# Controller_Power_Sliced.net
KiCad netlist of a schematic drawn in EAGLE
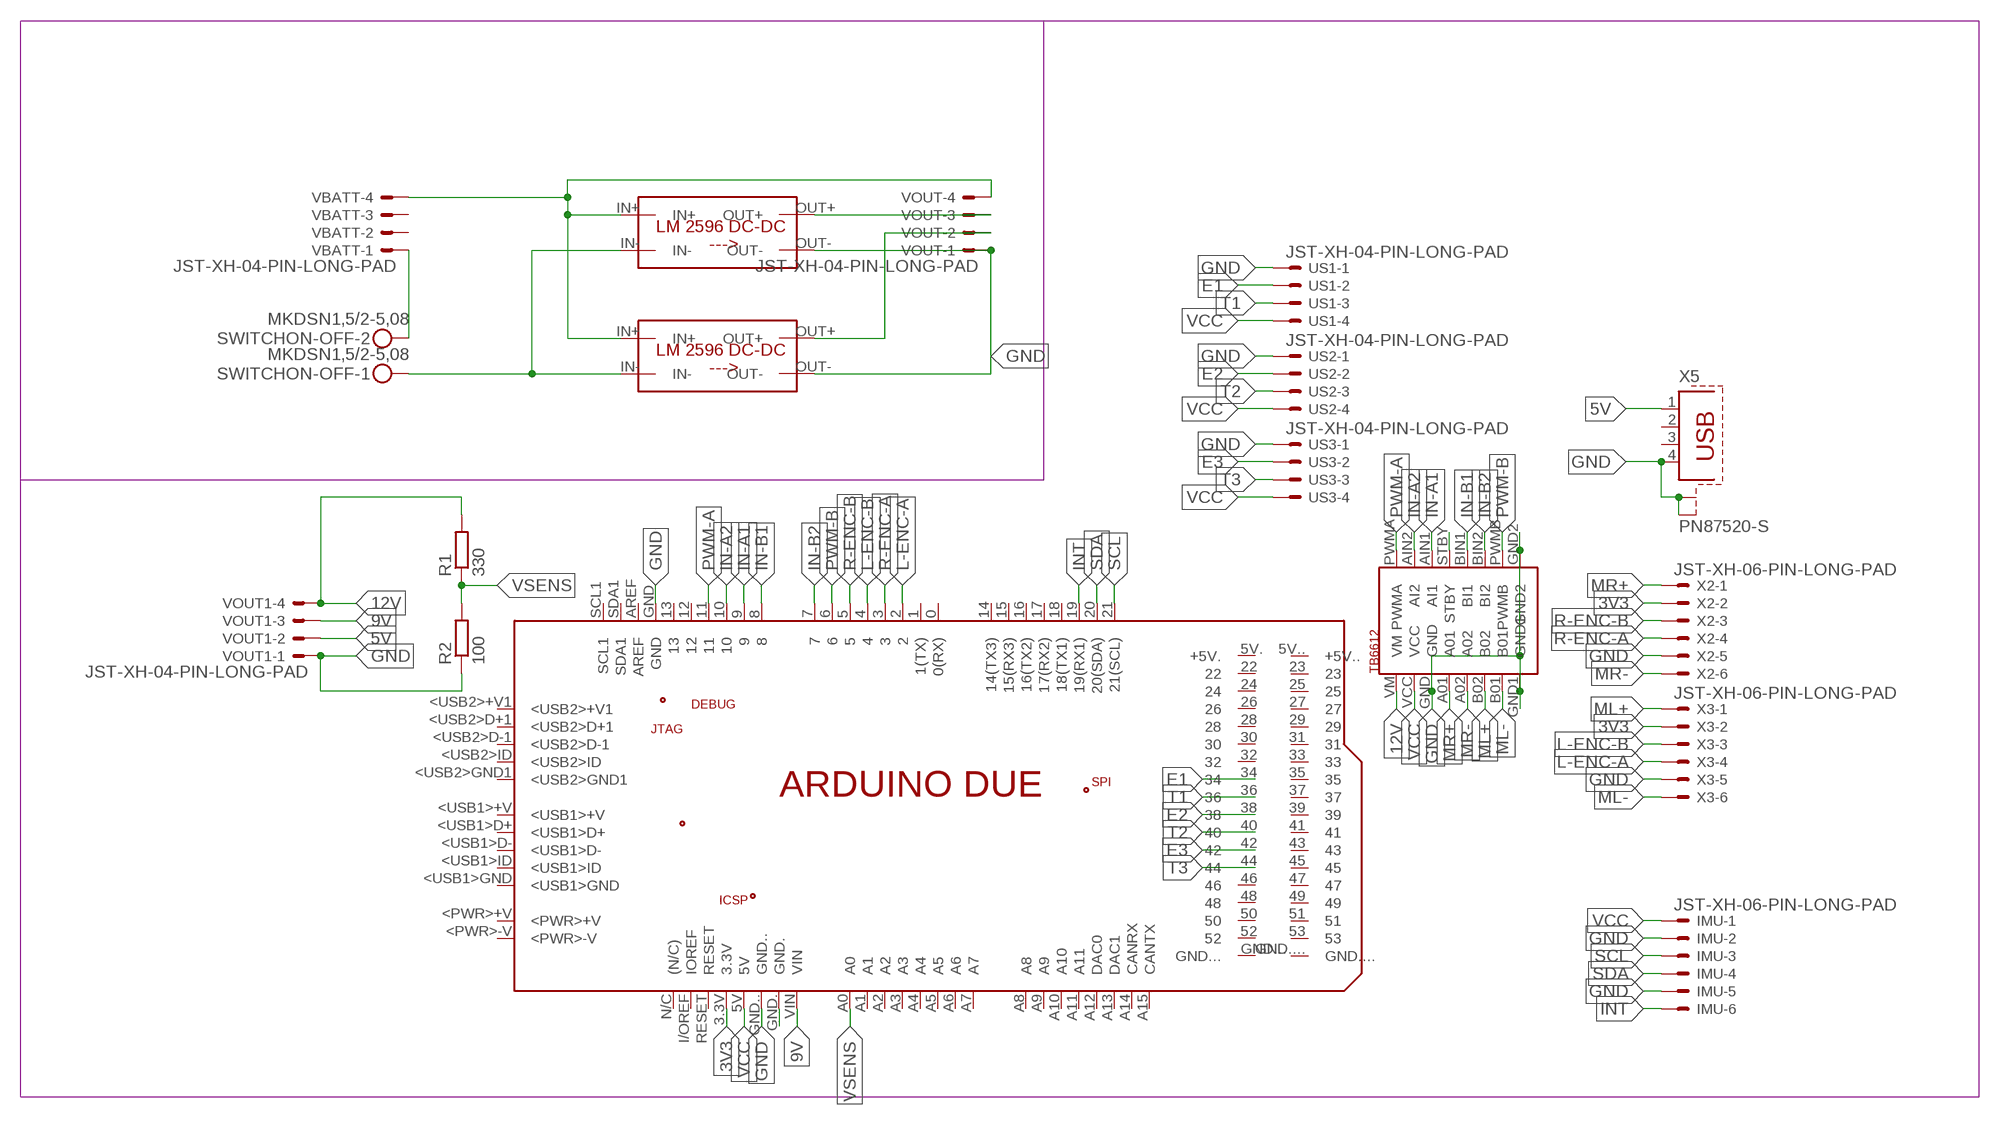
[diagram p0: schematic, sheet 1]

(export (version "E")
  (design (tool "Eeschema 10.0.6"))
  (components
    (comp (ref "IMU")
      (value "JST-XH-06-PIN-LONG-PAD")
      (footprint "eagle-import:JST-XH-06-PACKAGE-LONG-PAD")
      (libsource (lib "eagle-import") (part "JST-XH-06-PIN-LONG-PAD"))
    )
    (comp (ref "PCB1")
      (value "ARDUINO_DUE")
      (footprint "eagle-import:ARDUINO_DUE")
      (libsource (lib "eagle-import") (part "ARDUINO_DUE"))
    )
    (comp (ref "R1")
      (value "330")
      (footprint "eagle-import:R1206")
      (libsource (lib "eagle-import") (part "R-EU_R1206"))
    )
    (comp (ref "R2")
      (value "100")
      (footprint "eagle-import:R1206")
      (libsource (lib "eagle-import") (part "R-EU_R1206"))
    )
    (comp (ref "SWITCHON-OFF")
      (value "MKDSN1,5/2-5,08")
      (footprint "eagle-import:MKDSN1,5_2-5,08")
      (libsource (lib "eagle-import") (part "MKDSN1,5/2-5,08"))
    )
    (comp (ref "U$1")
      (value "LM2596_MODBUCK")
      (footprint "eagle-import:LM2596_MOD")
      (libsource (lib "eagle-import") (part "LM2596_MODBUCK"))
    )
    (comp (ref "U$2")
      (value "LM2596_MODBUCK")
      (footprint "eagle-import:LM2596_MOD")
      (libsource (lib "eagle-import") (part "LM2596_MODBUCK"))
    )
    (comp (ref "U$3")
      (value "TB6612")
      (footprint "eagle-import:TB6612")
      (libsource (lib "eagle-import") (part "TB6612"))
    )
    (comp (ref "US1")
      (value "JST-XH-04-PIN-LONG-PAD")
      (footprint "eagle-import:JST-XH-04-PACKAGE-LONG-PAD")
      (libsource (lib "eagle-import") (part "JST-XH-04-PIN-LONG-PAD"))
    )
    (comp (ref "US2")
      (value "JST-XH-04-PIN-LONG-PAD")
      (footprint "eagle-import:JST-XH-04-PACKAGE-LONG-PAD")
      (libsource (lib "eagle-import") (part "JST-XH-04-PIN-LONG-PAD"))
    )
    (comp (ref "US3")
      (value "JST-XH-04-PIN-LONG-PAD")
      (footprint "eagle-import:JST-XH-04-PACKAGE-LONG-PAD")
      (libsource (lib "eagle-import") (part "JST-XH-04-PIN-LONG-PAD"))
    )
    (comp (ref "VBATT")
      (value "JST-XH-04-PIN-LONG-PAD")
      (footprint "eagle-import:JST-XH-04-PACKAGE-LONG-PAD")
      (libsource (lib "eagle-import") (part "JST-XH-04-PIN-LONG-PAD"))
    )
    (comp (ref "VOUT")
      (value "JST-XH-04-PIN-LONG-PAD")
      (footprint "eagle-import:JST-XH-04-PACKAGE-LONG-PAD")
      (libsource (lib "eagle-import") (part "JST-XH-04-PIN-LONG-PAD"))
    )
    (comp (ref "VOUT1")
      (value "JST-XH-04-PIN-LONG-PAD")
      (footprint "eagle-import:JST-XH-04-PACKAGE-LONG-PAD")
      (libsource (lib "eagle-import") (part "JST-XH-04-PIN-LONG-PAD"))
    )
    (comp (ref "X2")
      (value "JST-XH-06-PIN-LONG-PAD")
      (footprint "eagle-import:JST-XH-06-PACKAGE-LONG-PAD")
      (libsource (lib "eagle-import") (part "JST-XH-06-PIN-LONG-PAD"))
    )
    (comp (ref "X3")
      (value "JST-XH-06-PIN-LONG-PAD")
      (footprint "eagle-import:JST-XH-06-PACKAGE-LONG-PAD")
      (libsource (lib "eagle-import") (part "JST-XH-06-PIN-LONG-PAD"))
    )
    (comp (ref "X5")
      (value "PN87520-S")
      (footprint "eagle-import:PN87520-S")
      (libsource (lib "eagle-import") (part "PN87520-S"))
    )
  )
  (nets
    (net (code "1") (name "3V3") (class "Default")
      (node (ref "PCB1") (pin "3.3V") (pinfunction "3.3V_3.3V") (pintype "bidirectional"))
      (node (ref "X2") (pin "2") (pinfunction "S_2") (pintype "passive"))
      (node (ref "X3") (pin "2") (pinfunction "S_2") (pintype "passive"))
    )
    (net (code "2") (name "5V") (class "Default")
      (node (ref "VOUT1") (pin "2") (pinfunction "S_2") (pintype "passive"))
      (node (ref "X5") (pin "1") (pinfunction "1_1") (pintype "passive"))
    )
    (net (code "3") (name "9V") (class "Default")
      (node (ref "PCB1") (pin "VIN") (pinfunction "VIN_VIN") (pintype "bidirectional"))
      (node (ref "VOUT1") (pin "3") (pinfunction "S_3") (pintype "passive"))
    )
    (net (code "4") (name "12V") (class "Default")
      (node (ref "R1") (pin "2") (pinfunction "2_2") (pintype "passive"))
      (node (ref "U$3") (pin "VM") (pinfunction "VM_VM") (pintype "bidirectional"))
      (node (ref "VOUT1") (pin "4") (pinfunction "S_4") (pintype "passive"))
    )
    (net (code "5") (name "E1") (class "Default")
      (node (ref "PCB1") (pin "34") (pinfunction "34_34") (pintype "bidirectional"))
      (node (ref "US1") (pin "2") (pinfunction "S_2") (pintype "passive"))
    )
    (net (code "6") (name "E2") (class "Default")
      (node (ref "PCB1") (pin "38") (pinfunction "38_38") (pintype "bidirectional"))
      (node (ref "US2") (pin "2") (pinfunction "S_2") (pintype "passive"))
    )
    (net (code "7") (name "E3") (class "Default")
      (node (ref "PCB1") (pin "42") (pinfunction "42_42") (pintype "bidirectional"))
      (node (ref "US3") (pin "2") (pinfunction "S_2") (pintype "passive"))
    )
    (net (code "8") (name "GND") (class "Default")
      (node (ref "IMU") (pin "2") (pinfunction "S_2") (pintype "passive"))
      (node (ref "IMU") (pin "5") (pinfunction "S_5") (pintype "passive"))
      (node (ref "PCB1") (pin "GND") (pinfunction "GND_GND") (pintype "bidirectional"))
      (node (ref "PCB1") (pin "GND..") (pinfunction "GND.._GND..") (pintype "bidirectional"))
      (node (ref "R2") (pin "1") (pinfunction "1_1") (pintype "passive"))
      (node (ref "U$1") (pin "OUT-") (pinfunction "OUT-_OUT-") (pintype "bidirectional"))
      (node (ref "U$2") (pin "OUT-") (pinfunction "OUT-_OUT-") (pintype "bidirectional"))
      (node (ref "U$3") (pin "GND") (pinfunction "GND_GND") (pintype "power_in"))
      (node (ref "U$3") (pin "GND1") (pinfunction "GND1_GND1") (pintype "power_in"))
      (node (ref "U$3") (pin "GND2") (pinfunction "GND2_GND2") (pintype "power_in"))
      (node (ref "US1") (pin "1") (pinfunction "S_1") (pintype "passive"))
      (node (ref "US2") (pin "1") (pinfunction "S_1") (pintype "passive"))
      (node (ref "US3") (pin "1") (pinfunction "S_1") (pintype "passive"))
      (node (ref "VOUT") (pin "1") (pinfunction "S_1") (pintype "passive"))
      (node (ref "VOUT1") (pin "1") (pinfunction "S_1") (pintype "passive"))
      (node (ref "X2") (pin "5") (pinfunction "S_5") (pintype "passive"))
      (node (ref "X3") (pin "5") (pinfunction "S_5") (pintype "passive"))
      (node (ref "X5") (pin "4") (pinfunction "4_4") (pintype "passive"))
      (node (ref "X5") (pin "S1") (pinfunction "S1_S1") (pintype "passive"))
      (node (ref "X5") (pin "S2") (pinfunction "S2_S2") (pintype "passive"))
    )
    (net (code "9") (name "IN-A1") (class "Default")
      (node (ref "PCB1") (pin "9") (pinfunction "9_9") (pintype "bidirectional"))
      (node (ref "U$3") (pin "AIN1") (pinfunction "AI1_AIN1") (pintype "bidirectional"))
    )
    (net (code "10") (name "IN-A2") (class "Default")
      (node (ref "PCB1") (pin "10") (pinfunction "10_10") (pintype "bidirectional"))
      (node (ref "U$3") (pin "AIN2") (pinfunction "AI2_AIN2") (pintype "bidirectional"))
    )
    (net (code "11") (name "IN-B1") (class "Default")
      (node (ref "PCB1") (pin "8") (pinfunction "8_8") (pintype "bidirectional"))
      (node (ref "U$3") (pin "BIN1") (pinfunction "BI1_BIN1") (pintype "bidirectional"))
    )
    (net (code "12") (name "IN-B2") (class "Default")
      (node (ref "PCB1") (pin "7") (pinfunction "7_7") (pintype "bidirectional"))
      (node (ref "U$3") (pin "BIN2") (pinfunction "BI2_BIN2") (pintype "bidirectional"))
    )
    (net (code "13") (name "INT") (class "Default")
      (node (ref "IMU") (pin "6") (pinfunction "S_6") (pintype "passive"))
      (node (ref "PCB1") (pin "19") (pinfunction "19(RX1)_19") (pintype "bidirectional"))
    )
    (net (code "14") (name "L-ENC-A") (class "Default")
      (node (ref "PCB1") (pin "2") (pinfunction "2_2") (pintype "bidirectional"))
      (node (ref "X3") (pin "4") (pinfunction "S_4") (pintype "passive"))
    )
    (net (code "15") (name "L-ENC-B") (class "Default")
      (node (ref "PCB1") (pin "4") (pinfunction "4_4") (pintype "bidirectional"))
      (node (ref "X3") (pin "3") (pinfunction "S_3") (pintype "passive"))
    )
    (net (code "16") (name "ML+") (class "Default")
      (node (ref "U$3") (pin "B02") (pinfunction "B02_B02") (pintype "bidirectional"))
      (node (ref "X3") (pin "1") (pinfunction "S_1") (pintype "passive"))
    )
    (net (code "17") (name "ML-") (class "Default")
      (node (ref "U$3") (pin "B01") (pinfunction "B01_B01") (pintype "bidirectional"))
      (node (ref "X3") (pin "6") (pinfunction "S_6") (pintype "passive"))
    )
    (net (code "18") (name "MR+") (class "Default")
      (node (ref "U$3") (pin "A01") (pinfunction "A01_A01") (pintype "bidirectional"))
      (node (ref "X2") (pin "1") (pinfunction "S_1") (pintype "passive"))
    )
    (net (code "19") (name "MR-") (class "Default")
      (node (ref "U$3") (pin "A02") (pinfunction "A02_A02") (pintype "bidirectional"))
      (node (ref "X2") (pin "6") (pinfunction "S_6") (pintype "passive"))
    )
    (net (code "20") (name "Net-(SWITCHON-OFFA-KL)") (class "Default")
      (node (ref "SWITCHON-OFF") (pin "1") (pinfunction "KL_1") (pintype "passive"))
      (node (ref "U$1") (pin "IN-") (pinfunction "IN-_IN-") (pintype "bidirectional"))
      (node (ref "U$2") (pin "IN-") (pinfunction "IN-_IN-") (pintype "bidirectional"))
    )
    (net (code "21") (name "Net-(SWITCHON-OFFB-KL)") (class "Default")
      (node (ref "SWITCHON-OFF") (pin "2") (pinfunction "KL_2") (pintype "passive"))
      (node (ref "VBATT") (pin "1") (pinfunction "S_1") (pintype "passive"))
    )
    (net (code "22") (name "Net-(VBATTD-S)") (class "Default")
      (node (ref "U$1") (pin "IN+") (pinfunction "IN+_IN+") (pintype "bidirectional"))
      (node (ref "U$2") (pin "IN+") (pinfunction "IN+_IN+") (pintype "bidirectional"))
      (node (ref "VBATT") (pin "4") (pinfunction "S_4") (pintype "passive"))
      (node (ref "VOUT") (pin "4") (pinfunction "S_4") (pintype "passive"))
    )
    (net (code "23") (name "Net-(VOUTB-S)") (class "Default")
      (node (ref "U$1") (pin "OUT+") (pinfunction "OUT+_OUT+") (pintype "bidirectional"))
      (node (ref "VOUT") (pin "2") (pinfunction "S_2") (pintype "passive"))
    )
    (net (code "24") (name "Net-(VOUTC-S)") (class "Default")
      (node (ref "U$2") (pin "OUT+") (pinfunction "OUT+_OUT+") (pintype "bidirectional"))
      (node (ref "VOUT") (pin "3") (pinfunction "S_3") (pintype "passive"))
    )
    (net (code "25") (name "PWM-A") (class "Default")
      (node (ref "PCB1") (pin "11") (pinfunction "11_11") (pintype "bidirectional"))
      (node (ref "U$3") (pin "PWMA") (pinfunction "PWMA_PWMA") (pintype "bidirectional"))
    )
    (net (code "26") (name "PWM-B") (class "Default")
      (node (ref "PCB1") (pin "6") (pinfunction "6_6") (pintype "bidirectional"))
      (node (ref "U$3") (pin "PWMB") (pinfunction "PWMB_PWMB") (pintype "bidirectional"))
    )
    (net (code "27") (name "R-ENC-A") (class "Default")
      (node (ref "PCB1") (pin "3") (pinfunction "3_3") (pintype "bidirectional"))
      (node (ref "X2") (pin "4") (pinfunction "S_4") (pintype "passive"))
    )
    (net (code "28") (name "R-ENC-B") (class "Default")
      (node (ref "PCB1") (pin "5") (pinfunction "5_5") (pintype "bidirectional"))
      (node (ref "X2") (pin "3") (pinfunction "S_3") (pintype "passive"))
    )
    (net (code "29") (name "SCL") (class "Default")
      (node (ref "IMU") (pin "3") (pinfunction "S_3") (pintype "passive"))
      (node (ref "PCB1") (pin "21") (pinfunction "21(SCL)_21") (pintype "bidirectional"))
    )
    (net (code "30") (name "SDA") (class "Default")
      (node (ref "IMU") (pin "4") (pinfunction "S_4") (pintype "passive"))
      (node (ref "PCB1") (pin "20") (pinfunction "20(SDA)_20") (pintype "bidirectional"))
    )
    (net (code "31") (name "T1") (class "Default")
      (node (ref "PCB1") (pin "36") (pinfunction "36_36") (pintype "bidirectional"))
      (node (ref "US1") (pin "3") (pinfunction "S_3") (pintype "passive"))
    )
    (net (code "32") (name "T2") (class "Default")
      (node (ref "PCB1") (pin "40") (pinfunction "40_40") (pintype "bidirectional"))
      (node (ref "US2") (pin "3") (pinfunction "S_3") (pintype "passive"))
    )
    (net (code "33") (name "T3") (class "Default")
      (node (ref "PCB1") (pin "44") (pinfunction "44_44") (pintype "bidirectional"))
      (node (ref "US3") (pin "3") (pinfunction "S_3") (pintype "passive"))
    )
    (net (code "34") (name "VCC") (class "Default")
      (node (ref "IMU") (pin "1") (pinfunction "S_1") (pintype "passive"))
      (node (ref "PCB1") (pin "5V") (pinfunction "5V_5V") (pintype "bidirectional"))
      (node (ref "U$3") (pin "VCC") (pinfunction "VCC_VCC") (pintype "bidirectional"))
      (node (ref "US1") (pin "4") (pinfunction "S_4") (pintype "passive"))
      (node (ref "US2") (pin "4") (pinfunction "S_4") (pintype "passive"))
      (node (ref "US3") (pin "4") (pinfunction "S_4") (pintype "passive"))
    )
    (net (code "35") (name "VSENS") (class "Default")
      (node (ref "PCB1") (pin "A0") (pinfunction "A0_A0") (pintype "bidirectional"))
      (node (ref "R1") (pin "1") (pinfunction "1_1") (pintype "passive"))
      (node (ref "R2") (pin "2") (pinfunction "2_2") (pintype "passive"))
    )
    (net (code "36") (name "unconnected-(PCB1-(N{slash}C)-PadN{slash}C)") (class "Default")
      (node (ref "PCB1") (pin "N/C") (pinfunction "(N/C)_N/C") (pintype "bidirectional"))
    )
    (net (code "37") (name "unconnected-(PCB1-+5V.-Pad5V.)") (class "Default")
      (node (ref "PCB1") (pin "5V.") (pinfunction "+5V._5V.") (pintype "bidirectional"))
    )
    (net (code "38") (name "unconnected-(PCB1-+5V..-Pad5V..)") (class "Default")
      (node (ref "PCB1") (pin "5V..") (pinfunction "+5V.._5V..") (pintype "bidirectional"))
    )
    (net (code "39") (name "unconnected-(PCB1-0(RX)-Pad0)") (class "Default")
      (node (ref "PCB1") (pin "0") (pinfunction "0(RX)_0") (pintype "bidirectional"))
    )
    (net (code "40") (name "unconnected-(PCB1-1(TX)-Pad1)") (class "Default")
      (node (ref "PCB1") (pin "1") (pinfunction "1(TX)_1") (pintype "bidirectional"))
    )
    (net (code "41") (name "unconnected-(PCB1-14(TX3)-Pad14)") (class "Default")
      (node (ref "PCB1") (pin "14") (pinfunction "14(TX3)_14") (pintype "bidirectional"))
    )
    (net (code "42") (name "unconnected-(PCB1-15(RX3)-Pad15)") (class "Default")
      (node (ref "PCB1") (pin "15") (pinfunction "15(RX3)_15") (pintype "bidirectional"))
    )
    (net (code "43") (name "unconnected-(PCB1-16(TX2)-Pad16)") (class "Default")
      (node (ref "PCB1") (pin "16") (pinfunction "16(TX2)_16") (pintype "bidirectional"))
    )
    (net (code "44") (name "unconnected-(PCB1-17(RX2)-Pad17)") (class "Default")
      (node (ref "PCB1") (pin "17") (pinfunction "17(RX2)_17") (pintype "bidirectional"))
    )
    (net (code "45") (name "unconnected-(PCB1-18(TX1)-Pad18)") (class "Default")
      (node (ref "PCB1") (pin "18") (pinfunction "18(TX1)_18") (pintype "bidirectional"))
    )
    (net (code "46") (name "unconnected-(PCB1-CANRX-PadA14)") (class "Default")
      (node (ref "PCB1") (pin "A14") (pinfunction "CANRX_A14") (pintype "bidirectional"))
    )
    (net (code "47") (name "unconnected-(PCB1-CANTX-PadA15)") (class "Default")
      (node (ref "PCB1") (pin "A15") (pinfunction "CANTX_A15") (pintype "bidirectional"))
    )
    (net (code "48") (name "unconnected-(PCB1-DAC0-PadA12)") (class "Default")
      (node (ref "PCB1") (pin "A12") (pinfunction "DAC0_A12") (pintype "bidirectional"))
    )
    (net (code "49") (name "unconnected-(PCB1-DAC1-PadA13)") (class "Default")
      (node (ref "PCB1") (pin "A13") (pinfunction "DAC1_A13") (pintype "bidirectional"))
    )
    (net (code "50") (name "unconnected-(PCB1-IOREF-PadI{slash}OREF)") (class "Default")
      (node (ref "PCB1") (pin "I/OREF") (pinfunction "IOREF_I/OREF") (pintype "bidirectional"))
    )
    (net (code "51") (name "unconnected-(PCB1-Pad+3.3V)") (class "Default")
      (node (ref "PCB1") (pin "+3.3V") (pinfunction "+3.3V_+3.3V") (pintype "bidirectional"))
    )
    (net (code "52") (name "unconnected-(PCB1-Pad+5V)") (class "Default")
      (node (ref "PCB1") (pin "+5V") (pinfunction "+5V_+5V") (pintype "bidirectional"))
    )
    (net (code "53") (name "unconnected-(PCB1-Pad+5V_)") (class "Default")
      (node (ref "PCB1") (pin "+5V_") (pinfunction "+5V__+5V_") (pintype "bidirectional"))
    )
    (net (code "54") (name "unconnected-(PCB1-Pad12)") (class "Default")
      (node (ref "PCB1") (pin "12") (pinfunction "12_12") (pintype "bidirectional"))
    )
    (net (code "55") (name "unconnected-(PCB1-Pad13)") (class "Default")
      (node (ref "PCB1") (pin "13") (pinfunction "13_13") (pintype "bidirectional"))
    )
    (net (code "56") (name "unconnected-(PCB1-Pad22)") (class "Default")
      (node (ref "PCB1") (pin "22") (pinfunction "22_22") (pintype "bidirectional"))
    )
    (net (code "57") (name "unconnected-(PCB1-Pad23)") (class "Default")
      (node (ref "PCB1") (pin "23") (pinfunction "23_23") (pintype "bidirectional"))
    )
    (net (code "58") (name "unconnected-(PCB1-Pad24)") (class "Default")
      (node (ref "PCB1") (pin "24") (pinfunction "24_24") (pintype "bidirectional"))
    )
    (net (code "59") (name "unconnected-(PCB1-Pad25)") (class "Default")
      (node (ref "PCB1") (pin "25") (pinfunction "25_25") (pintype "bidirectional"))
    )
    (net (code "60") (name "unconnected-(PCB1-Pad26)") (class "Default")
      (node (ref "PCB1") (pin "26") (pinfunction "26_26") (pintype "bidirectional"))
    )
    (net (code "61") (name "unconnected-(PCB1-Pad27)") (class "Default")
      (node (ref "PCB1") (pin "27") (pinfunction "27_27") (pintype "bidirectional"))
    )
    (net (code "62") (name "unconnected-(PCB1-Pad28)") (class "Default")
      (node (ref "PCB1") (pin "28") (pinfunction "28_28") (pintype "bidirectional"))
    )
    (net (code "63") (name "unconnected-(PCB1-Pad29)") (class "Default")
      (node (ref "PCB1") (pin "29") (pinfunction "29_29") (pintype "bidirectional"))
    )
    (net (code "64") (name "unconnected-(PCB1-Pad30)") (class "Default")
      (node (ref "PCB1") (pin "30") (pinfunction "30_30") (pintype "bidirectional"))
    )
    (net (code "65") (name "unconnected-(PCB1-Pad31)") (class "Default")
      (node (ref "PCB1") (pin "31") (pinfunction "31_31") (pintype "bidirectional"))
    )
    (net (code "66") (name "unconnected-(PCB1-Pad32)") (class "Default")
      (node (ref "PCB1") (pin "32") (pinfunction "32_32") (pintype "bidirectional"))
    )
    (net (code "67") (name "unconnected-(PCB1-Pad33)") (class "Default")
      (node (ref "PCB1") (pin "33") (pinfunction "33_33") (pintype "bidirectional"))
    )
    (net (code "68") (name "unconnected-(PCB1-Pad35)") (class "Default")
      (node (ref "PCB1") (pin "35") (pinfunction "35_35") (pintype "bidirectional"))
    )
    (net (code "69") (name "unconnected-(PCB1-Pad37)") (class "Default")
      (node (ref "PCB1") (pin "37") (pinfunction "37_37") (pintype "bidirectional"))
    )
    (net (code "70") (name "unconnected-(PCB1-Pad39)") (class "Default")
      (node (ref "PCB1") (pin "39") (pinfunction "39_39") (pintype "bidirectional"))
    )
    (net (code "71") (name "unconnected-(PCB1-Pad41)") (class "Default")
      (node (ref "PCB1") (pin "41") (pinfunction "41_41") (pintype "bidirectional"))
    )
    (net (code "72") (name "unconnected-(PCB1-Pad43)") (class "Default")
      (node (ref "PCB1") (pin "43") (pinfunction "43_43") (pintype "bidirectional"))
    )
    (net (code "73") (name "unconnected-(PCB1-Pad45)") (class "Default")
      (node (ref "PCB1") (pin "45") (pinfunction "45_45") (pintype "bidirectional"))
    )
    (net (code "74") (name "unconnected-(PCB1-Pad46)") (class "Default")
      (node (ref "PCB1") (pin "46") (pinfunction "46_46") (pintype "bidirectional"))
    )
    (net (code "75") (name "unconnected-(PCB1-Pad47)") (class "Default")
      (node (ref "PCB1") (pin "47") (pinfunction "47_47") (pintype "bidirectional"))
    )
    (net (code "76") (name "unconnected-(PCB1-Pad48)") (class "Default")
      (node (ref "PCB1") (pin "48") (pinfunction "48_48") (pintype "bidirectional"))
    )
    (net (code "77") (name "unconnected-(PCB1-Pad49)") (class "Default")
      (node (ref "PCB1") (pin "49") (pinfunction "49_49") (pintype "bidirectional"))
    )
    (net (code "78") (name "unconnected-(PCB1-Pad50)") (class "Default")
      (node (ref "PCB1") (pin "50") (pinfunction "50_50") (pintype "bidirectional"))
    )
    (net (code "79") (name "unconnected-(PCB1-Pad51)") (class "Default")
      (node (ref "PCB1") (pin "51") (pinfunction "51_51") (pintype "bidirectional"))
    )
    (net (code "80") (name "unconnected-(PCB1-Pad52)") (class "Default")
      (node (ref "PCB1") (pin "52") (pinfunction "52_52") (pintype "bidirectional"))
    )
    (net (code "81") (name "unconnected-(PCB1-Pad53)") (class "Default")
      (node (ref "PCB1") (pin "53") (pinfunction "53_53") (pintype "bidirectional"))
    )
    (net (code "82") (name "unconnected-(PCB1-Pad<PWR>+V)") (class "Default")
      (node (ref "PCB1") (pin "<PWR>+V") (pinfunction "<PWR>+V_<PWR>+V") (pintype "bidirectional"))
    )
    (net (code "83") (name "unconnected-(PCB1-Pad<PWR>-V)") (class "Default")
      (node (ref "PCB1") (pin "<PWR>-V") (pinfunction "<PWR>-V_<PWR>-V") (pintype "bidirectional"))
    )
    (net (code "84") (name "unconnected-(PCB1-Pad<USB1>+V)") (class "Default")
      (node (ref "PCB1") (pin "<USB1>+V") (pinfunction "<USB1>+V_<USB1>+V") (pintype "bidirectional"))
    )
    (net (code "85") (name "unconnected-(PCB1-Pad<USB1>D+)") (class "Default")
      (node (ref "PCB1") (pin "<USB1>D+") (pinfunction "<USB1>D+_<USB1>D+") (pintype "bidirectional"))
    )
    (net (code "86") (name "unconnected-(PCB1-Pad<USB1>D-)") (class "Default")
      (node (ref "PCB1") (pin "<USB1>D-") (pinfunction "<USB1>D-_<USB1>D-") (pintype "bidirectional"))
    )
    (net (code "87") (name "unconnected-(PCB1-Pad<USB1>GND)") (class "Default")
      (node (ref "PCB1") (pin "<USB1>GND") (pinfunction "<USB1>GND_<USB1>GND") (pintype "bidirectional"))
    )
    (net (code "88") (name "unconnected-(PCB1-Pad<USB1>ID)") (class "Default")
      (node (ref "PCB1") (pin "<USB1>ID") (pinfunction "<USB1>ID_<USB1>ID") (pintype "bidirectional"))
    )
    (net (code "89") (name "unconnected-(PCB1-Pad<USB2>+V1)") (class "Default")
      (node (ref "PCB1") (pin "<USB2>+V1") (pinfunction "<USB2>+V1_<USB2>+V1") (pintype "bidirectional"))
    )
    (net (code "90") (name "unconnected-(PCB1-Pad<USB2>D+1)") (class "Default")
      (node (ref "PCB1") (pin "<USB2>D+1") (pinfunction "<USB2>D+1_<USB2>D+1") (pintype "bidirectional"))
    )
    (net (code "91") (name "unconnected-(PCB1-Pad<USB2>D-1)") (class "Default")
      (node (ref "PCB1") (pin "<USB2>D-1") (pinfunction "<USB2>D-1_<USB2>D-1") (pintype "bidirectional"))
    )
    (net (code "92") (name "unconnected-(PCB1-Pad<USB2>GND1)") (class "Default")
      (node (ref "PCB1") (pin "<USB2>GND1") (pinfunction "<USB2>GND1_<USB2>GND1") (pintype "bidirectional"))
    )
    (net (code "93") (name "unconnected-(PCB1-Pad<USB2>ID)") (class "Default")
      (node (ref "PCB1") (pin "<USB2>ID") (pinfunction "<USB2>ID_<USB2>ID") (pintype "bidirectional"))
    )
    (net (code "94") (name "unconnected-(PCB1-PadA1)") (class "Default")
      (node (ref "PCB1") (pin "A1") (pinfunction "A1_A1") (pintype "bidirectional"))
    )
    (net (code "95") (name "unconnected-(PCB1-PadA2)") (class "Default")
      (node (ref "PCB1") (pin "A2") (pinfunction "A2_A2") (pintype "bidirectional"))
    )
    (net (code "96") (name "unconnected-(PCB1-PadA3)") (class "Default")
      (node (ref "PCB1") (pin "A3") (pinfunction "A3_A3") (pintype "bidirectional"))
    )
    (net (code "97") (name "unconnected-(PCB1-PadA4)") (class "Default")
      (node (ref "PCB1") (pin "A4") (pinfunction "A4_A4") (pintype "bidirectional"))
    )
    (net (code "98") (name "unconnected-(PCB1-PadA5)") (class "Default")
      (node (ref "PCB1") (pin "A5") (pinfunction "A5_A5") (pintype "bidirectional"))
    )
    (net (code "99") (name "unconnected-(PCB1-PadA6)") (class "Default")
      (node (ref "PCB1") (pin "A6") (pinfunction "A6_A6") (pintype "bidirectional"))
    )
    (net (code "100") (name "unconnected-(PCB1-PadA7)") (class "Default")
      (node (ref "PCB1") (pin "A7") (pinfunction "A7_A7") (pintype "bidirectional"))
    )
    (net (code "101") (name "unconnected-(PCB1-PadA8)") (class "Default")
      (node (ref "PCB1") (pin "A8") (pinfunction "A8_A8") (pintype "bidirectional"))
    )
    (net (code "102") (name "unconnected-(PCB1-PadA9)") (class "Default")
      (node (ref "PCB1") (pin "A9") (pinfunction "A9_A9") (pintype "bidirectional"))
    )
    (net (code "103") (name "unconnected-(PCB1-PadA10)") (class "Default")
      (node (ref "PCB1") (pin "A10") (pinfunction "A10_A10") (pintype "bidirectional"))
    )
    (net (code "104") (name "unconnected-(PCB1-PadA11)") (class "Default")
      (node (ref "PCB1") (pin "A11") (pinfunction "A11_A11") (pintype "bidirectional"))
    )
    (net (code "105") (name "unconnected-(PCB1-PadAREF)") (class "Default")
      (node (ref "PCB1") (pin "AREF") (pinfunction "AREF_AREF") (pintype "bidirectional"))
    )
    (net (code "106") (name "unconnected-(PCB1-PadGND.)") (class "Default")
      (node (ref "PCB1") (pin "GND.") (pinfunction "GND._GND.") (pintype "bidirectional"))
    )
    (net (code "107") (name "unconnected-(PCB1-PadGND...)") (class "Default")
      (node (ref "PCB1") (pin "GND...") (pinfunction "GND..._GND...") (pintype "bidirectional"))
    )
    (net (code "108") (name "unconnected-(PCB1-PadGND....)") (class "Default")
      (node (ref "PCB1") (pin "GND....") (pinfunction "GND...._GND....") (pintype "bidirectional"))
    )
    (net (code "109") (name "unconnected-(PCB1-PadGND1)") (class "Default")
      (node (ref "PCB1") (pin "GND1") (pinfunction "GND1_GND1") (pintype "bidirectional"))
    )
    (net (code "110") (name "unconnected-(PCB1-PadGND1.)") (class "Default")
      (node (ref "PCB1") (pin "GND1.") (pinfunction "GND1._GND1.") (pintype "bidirectional"))
    )
    (net (code "111") (name "unconnected-(PCB1-PadGND1..)") (class "Default")
      (node (ref "PCB1") (pin "GND1..") (pinfunction "GND1.._GND1..") (pintype "bidirectional"))
    )
    (net (code "112") (name "unconnected-(PCB1-PadGND1...)") (class "Default")
      (node (ref "PCB1") (pin "GND1...") (pinfunction "GND1..._GND1...") (pintype "bidirectional"))
    )
    (net (code "113") (name "unconnected-(PCB1-PadGND_)") (class "Default")
      (node (ref "PCB1") (pin "GND_") (pinfunction "GND__GND_") (pintype "bidirectional"))
    )
    (net (code "114") (name "unconnected-(PCB1-PadGND__)") (class "Default")
      (node (ref "PCB1") (pin "GND__") (pinfunction "GND___GND__") (pintype "bidirectional"))
    )
    (net (code "115") (name "unconnected-(PCB1-PadMISO)") (class "Default")
      (node (ref "PCB1") (pin "MISO") (pinfunction "MISO_MISO") (pintype "bidirectional"))
    )
    (net (code "116") (name "unconnected-(PCB1-PadMISO2)") (class "Default")
      (node (ref "PCB1") (pin "MISO2") (pinfunction "MISO2_MISO2") (pintype "bidirectional"))
    )
    (net (code "117") (name "unconnected-(PCB1-PadMOSI)") (class "Default")
      (node (ref "PCB1") (pin "MOSI") (pinfunction "MOSI_MOSI") (pintype "bidirectional"))
    )
    (net (code "118") (name "unconnected-(PCB1-PadMOSI2)") (class "Default")
      (node (ref "PCB1") (pin "MOSI2") (pinfunction "MOSI2_MOSI2") (pintype "bidirectional"))
    )
    (net (code "119") (name "unconnected-(PCB1-PadN{slash}C.)") (class "Default")
      (node (ref "PCB1") (pin "N/C.") (pinfunction "N/C._N/C.") (pintype "bidirectional"))
    )
    (net (code "120") (name "unconnected-(PCB1-PadRESET)") (class "Default")
      (node (ref "PCB1") (pin "RESET") (pinfunction "RESET_RESET") (pintype "bidirectional"))
    )
    (net (code "121") (name "unconnected-(PCB1-PadRESET.)") (class "Default")
      (node (ref "PCB1") (pin "RESET.") (pinfunction "RESET._RESET.") (pintype "bidirectional"))
    )
    (net (code "122") (name "unconnected-(PCB1-PadRESET..)") (class "Default")
      (node (ref "PCB1") (pin "RESET..") (pinfunction "RESET.._RESET..") (pintype "bidirectional"))
    )
    (net (code "123") (name "unconnected-(PCB1-PadRESET2)") (class "Default")
      (node (ref "PCB1") (pin "RESET2") (pinfunction "RESET2_RESET2") (pintype "bidirectional"))
    )
    (net (code "124") (name "unconnected-(PCB1-PadRESET_)") (class "Default")
      (node (ref "PCB1") (pin "RESET_") (pinfunction "RESET__RESET_") (pintype "bidirectional"))
    )
    (net (code "125") (name "unconnected-(PCB1-PadSCK)") (class "Default")
      (node (ref "PCB1") (pin "SCK") (pinfunction "SCK_SCK") (pintype "bidirectional"))
    )
    (net (code "126") (name "unconnected-(PCB1-PadSCK2)") (class "Default")
      (node (ref "PCB1") (pin "SCK2") (pinfunction "SCK2_SCK2") (pintype "bidirectional"))
    )
    (net (code "127") (name "unconnected-(PCB1-PadSCL1)") (class "Default")
      (node (ref "PCB1") (pin "SCL1") (pinfunction "SCL1_SCL1") (pintype "bidirectional"))
    )
    (net (code "128") (name "unconnected-(PCB1-PadSDA1)") (class "Default")
      (node (ref "PCB1") (pin "SDA1") (pinfunction "SDA1_SDA1") (pintype "bidirectional"))
    )
    (net (code "129") (name "unconnected-(PCB1-PadSWCLK)") (class "Default")
      (node (ref "PCB1") (pin "SWCLK") (pinfunction "SWCLK_SWCLK") (pintype "bidirectional"))
    )
    (net (code "130") (name "unconnected-(PCB1-PadSWDIO)") (class "Default")
      (node (ref "PCB1") (pin "SWDIO") (pinfunction "SWDIO_SWDIO") (pintype "bidirectional"))
    )
    (net (code "131") (name "unconnected-(PCB1-PadTCK)") (class "Default")
      (node (ref "PCB1") (pin "TCK") (pinfunction "TCK_TCK") (pintype "bidirectional"))
    )
    (net (code "132") (name "unconnected-(PCB1-PadTDI)") (class "Default")
      (node (ref "PCB1") (pin "TDI") (pinfunction "TDI_TDI") (pintype "bidirectional"))
    )
    (net (code "133") (name "unconnected-(PCB1-PadTDO)") (class "Default")
      (node (ref "PCB1") (pin "TDO") (pinfunction "TDO_TDO") (pintype "bidirectional"))
    )
    (net (code "134") (name "unconnected-(PCB1-PadTMS)") (class "Default")
      (node (ref "PCB1") (pin "TMS") (pinfunction "TMS_TMS") (pintype "bidirectional"))
    )
    (net (code "135") (name "unconnected-(U$3-PadSTBY)") (class "Default")
      (node (ref "U$3") (pin "STBY") (pinfunction "STBY_STBY") (pintype "bidirectional"))
    )
    (net (code "136") (name "unconnected-(VBATTB-S-Pad2)") (class "Default")
      (node (ref "VBATT") (pin "2") (pinfunction "S_2") (pintype "passive"))
    )
    (net (code "137") (name "unconnected-(VBATTC-S-Pad3)") (class "Default")
      (node (ref "VBATT") (pin "3") (pinfunction "S_3") (pintype "passive"))
    )
    (net (code "138") (name "unconnected-(X5-Pad2)") (class "Default")
      (node (ref "X5") (pin "2") (pinfunction "2_2") (pintype "passive"))
    )
    (net (code "139") (name "unconnected-(X5-Pad3)") (class "Default")
      (node (ref "X5") (pin "3") (pinfunction "3_3") (pintype "passive"))
    )
  )
)
